# vfd-driver.net
KiCad netlist of a schematic drawn in EAGLE
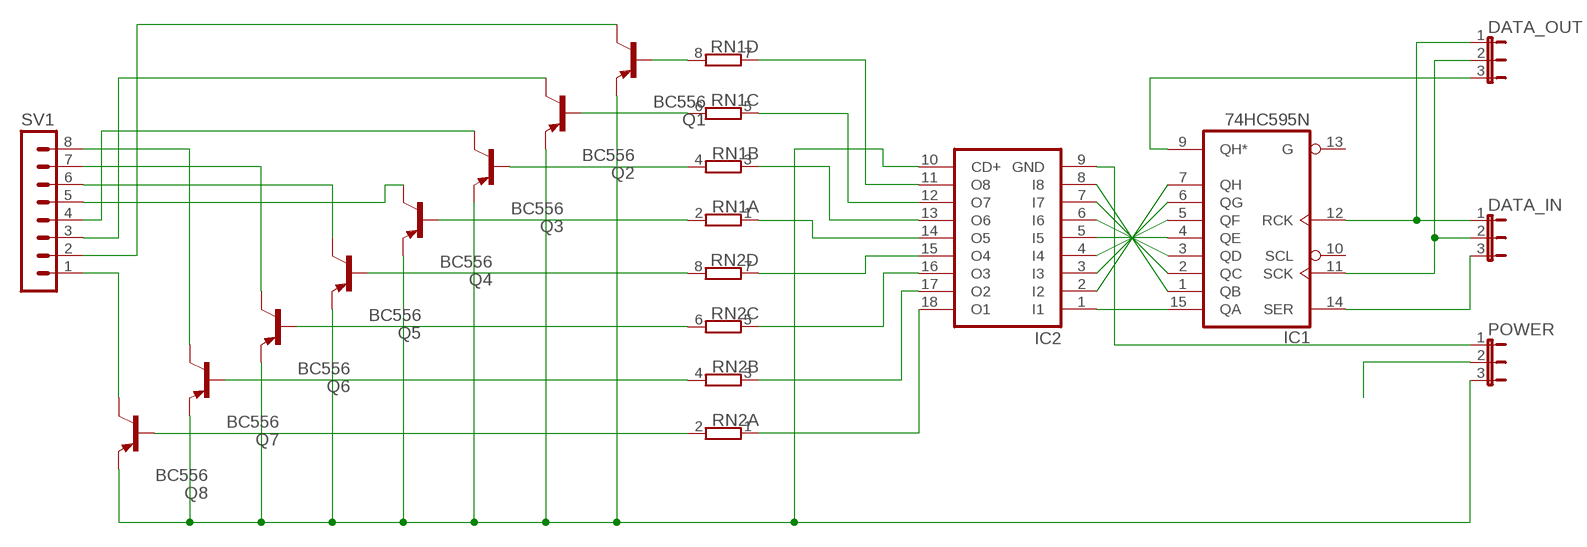
[diagram p0: schematic, sheet 1]

(export (version "E")
  (design (tool "Eeschema 10.0.6"))
  (components
    (comp (ref "DATA_IN")
      (value "JP2E")
      (footprint "eagle-import:JP2")
      (libsource (lib "eagle-import") (part "JP2E"))
    )
    (comp (ref "DATA_OUT")
      (value "JP2E")
      (footprint "eagle-import:JP2")
      (libsource (lib "eagle-import") (part "JP2E"))
    )
    (comp (ref "IC1")
      (value "74HC595N")
      (footprint "eagle-import:DIL16")
      (libsource (lib "eagle-import") (part "74595NHC"))
    )
    (comp (ref "IC2")
      (value "ULN2803A")
      (footprint "eagle-import:DIL18")
      (libsource (lib "eagle-import") (part "ULN2803A"))
    )
    (comp (ref "POWER")
      (value "JP2E")
      (footprint "eagle-import:JP2")
      (libsource (lib "eagle-import") (part "JP2E"))
    )
    (comp (ref "Q1")
      (value "BC556")
      (footprint "eagle-import:TO92-EBC")
      (libsource (lib "eagle-import") (part "BC556"))
    )
    (comp (ref "Q2")
      (value "BC556")
      (footprint "eagle-import:TO92-EBC")
      (libsource (lib "eagle-import") (part "BC556"))
    )
    (comp (ref "Q3")
      (value "BC556")
      (footprint "eagle-import:TO92-EBC")
      (libsource (lib "eagle-import") (part "BC556"))
    )
    (comp (ref "Q4")
      (value "BC556")
      (footprint "eagle-import:TO92-EBC")
      (libsource (lib "eagle-import") (part "BC556"))
    )
    (comp (ref "Q5")
      (value "BC556")
      (footprint "eagle-import:TO92-EBC")
      (libsource (lib "eagle-import") (part "BC556"))
    )
    (comp (ref "Q6")
      (value "BC556")
      (footprint "eagle-import:TO92-EBC")
      (libsource (lib "eagle-import") (part "BC556"))
    )
    (comp (ref "Q7")
      (value "BC556")
      (footprint "eagle-import:TO92-EBC")
      (libsource (lib "eagle-import") (part "BC556"))
    )
    (comp (ref "Q8")
      (value "BC556")
      (footprint "eagle-import:TO92-EBC")
      (libsource (lib "eagle-import") (part "BC556"))
    )
    (comp (ref "RN1")
      (value "E4R")
      (footprint "eagle-import:SIL8")
      (libsource (lib "eagle-import") (part "E4R"))
    )
    (comp (ref "RN2")
      (value "E4R")
      (footprint "eagle-import:SIL8")
      (libsource (lib "eagle-import") (part "E4R"))
    )
    (comp (ref "SV1")
      (value "MA08-1")
      (footprint "eagle-import:MA08-1")
      (libsource (lib "eagle-import") (part "MA08-1"))
    )
  )
  (nets
    (net (code "1") (name "Net-(IC1A-QA)") (class "Default")
      (node (ref "IC1") (pin "15") (pinfunction "QA_15") (pintype "tri_state"))
      (node (ref "IC2") (pin "1") (pinfunction "I1_1") (pintype "input"))
    )
    (net (code "2") (name "Net-(IC1A-QB)") (class "Default")
      (node (ref "IC1") (pin "1") (pinfunction "QB_1") (pintype "tri_state"))
      (node (ref "IC2") (pin "8") (pinfunction "I8_8") (pintype "input"))
    )
    (net (code "3") (name "Net-(IC1A-QC)") (class "Default")
      (node (ref "IC1") (pin "2") (pinfunction "QC_2") (pintype "tri_state"))
      (node (ref "IC2") (pin "7") (pinfunction "I7_7") (pintype "input"))
    )
    (net (code "4") (name "Net-(IC1A-QD)") (class "Default")
      (node (ref "IC1") (pin "3") (pinfunction "QD_3") (pintype "tri_state"))
      (node (ref "IC2") (pin "6") (pinfunction "I6_6") (pintype "input"))
    )
    (net (code "5") (name "Net-(IC1A-QE)") (class "Default")
      (node (ref "IC1") (pin "4") (pinfunction "QE_4") (pintype "tri_state"))
      (node (ref "IC2") (pin "5") (pinfunction "I5_5") (pintype "input"))
    )
    (net (code "6") (name "Net-(IC1A-QF)") (class "Default")
      (node (ref "IC1") (pin "5") (pinfunction "QF_5") (pintype "tri_state"))
      (node (ref "IC2") (pin "4") (pinfunction "I4_4") (pintype "input"))
    )
    (net (code "7") (name "Net-(IC1A-QG)") (class "Default")
      (node (ref "IC1") (pin "6") (pinfunction "QG_6") (pintype "tri_state"))
      (node (ref "IC2") (pin "3") (pinfunction "I3_3") (pintype "input"))
    )
    (net (code "8") (name "Net-(IC1A-QH)") (class "Default")
      (node (ref "IC1") (pin "7") (pinfunction "QH_7") (pintype "tri_state"))
      (node (ref "IC2") (pin "2") (pinfunction "I2_2") (pintype "input"))
    )
    (net (code "9") (name "Net-(IC1A-QH*)") (class "Default")
      (node (ref "DATA_OUT") (pin "3") (pinfunction "3_3") (pintype "passive"))
      (node (ref "IC1") (pin "9") (pinfunction "QH*_9") (pintype "tri_state"))
    )
    (net (code "10") (name "Net-(IC1A-RCK)") (class "Default")
      (node (ref "DATA_IN") (pin "1") (pinfunction "1_1") (pintype "passive"))
      (node (ref "DATA_OUT") (pin "1") (pinfunction "1_1") (pintype "passive"))
      (node (ref "IC1") (pin "12") (pinfunction "RCK_12") (pintype "input"))
    )
    (net (code "11") (name "Net-(IC1A-SCK)") (class "Default")
      (node (ref "DATA_IN") (pin "2") (pinfunction "2_2") (pintype "passive"))
      (node (ref "DATA_OUT") (pin "2") (pinfunction "2_2") (pintype "passive"))
      (node (ref "IC1") (pin "11") (pinfunction "SCK_11") (pintype "input"))
    )
    (net (code "12") (name "Net-(IC1A-SER)") (class "Default")
      (node (ref "DATA_IN") (pin "3") (pinfunction "3_3") (pintype "passive"))
      (node (ref "IC1") (pin "14") (pinfunction "SER_14") (pintype "input"))
    )
    (net (code "13") (name "Net-(IC2-CD+)") (class "Default")
      (node (ref "IC2") (pin "10") (pinfunction "CD+_10") (pintype "passive"))
      (node (ref "POWER") (pin "3") (pinfunction "3_3") (pintype "passive"))
      (node (ref "Q1") (pin "E") (pinfunction "E_E") (pintype "passive"))
      (node (ref "Q2") (pin "E") (pinfunction "E_E") (pintype "passive"))
      (node (ref "Q3") (pin "E") (pinfunction "E_E") (pintype "passive"))
      (node (ref "Q4") (pin "E") (pinfunction "E_E") (pintype "passive"))
      (node (ref "Q5") (pin "E") (pinfunction "E_E") (pintype "passive"))
      (node (ref "Q6") (pin "E") (pinfunction "E_E") (pintype "passive"))
      (node (ref "Q7") (pin "E") (pinfunction "E_E") (pintype "passive"))
      (node (ref "Q8") (pin "E") (pinfunction "E_E") (pintype "passive"))
    )
    (net (code "14") (name "Net-(IC2-GND)") (class "Default")
      (node (ref "IC2") (pin "9") (pinfunction "GND_9") (pintype "power_in"))
      (node (ref "POWER") (pin "1") (pinfunction "1_1") (pintype "passive"))
    )
    (net (code "15") (name "Net-(IC2-O1)") (class "Default")
      (node (ref "IC2") (pin "18") (pinfunction "O1_18") (pintype "open_collector"))
      (node (ref "RN2") (pin "1") (pinfunction "1_1") (pintype "passive"))
    )
    (net (code "16") (name "Net-(IC2-O2)") (class "Default")
      (node (ref "IC2") (pin "17") (pinfunction "O2_17") (pintype "open_collector"))
      (node (ref "RN2") (pin "3") (pinfunction "1_3") (pintype "passive"))
    )
    (net (code "17") (name "Net-(IC2-O3)") (class "Default")
      (node (ref "IC2") (pin "16") (pinfunction "O3_16") (pintype "open_collector"))
      (node (ref "RN2") (pin "5") (pinfunction "1_5") (pintype "passive"))
    )
    (net (code "18") (name "Net-(IC2-O4)") (class "Default")
      (node (ref "IC2") (pin "15") (pinfunction "O4_15") (pintype "open_collector"))
      (node (ref "RN2") (pin "7") (pinfunction "1_7") (pintype "passive"))
    )
    (net (code "19") (name "Net-(IC2-O5)") (class "Default")
      (node (ref "IC2") (pin "14") (pinfunction "O5_14") (pintype "open_collector"))
      (node (ref "RN1") (pin "1") (pinfunction "1_1") (pintype "passive"))
    )
    (net (code "20") (name "Net-(IC2-O6)") (class "Default")
      (node (ref "IC2") (pin "13") (pinfunction "O6_13") (pintype "open_collector"))
      (node (ref "RN1") (pin "3") (pinfunction "1_3") (pintype "passive"))
    )
    (net (code "21") (name "Net-(IC2-O7)") (class "Default")
      (node (ref "IC2") (pin "12") (pinfunction "O7_12") (pintype "open_collector"))
      (node (ref "RN1") (pin "5") (pinfunction "1_5") (pintype "passive"))
    )
    (net (code "22") (name "Net-(IC2-O8)") (class "Default")
      (node (ref "IC2") (pin "11") (pinfunction "O8_11") (pintype "open_collector"))
      (node (ref "RN1") (pin "7") (pinfunction "1_7") (pintype "passive"))
    )
    (net (code "23") (name "Net-(Q1-PadC)") (class "Default")
      (node (ref "Q1") (pin "C") (pinfunction "C_C") (pintype "passive"))
      (node (ref "SV1") (pin "2") (pinfunction "2_2") (pintype "passive"))
    )
    (net (code "24") (name "Net-(Q2-PadC)") (class "Default")
      (node (ref "Q2") (pin "C") (pinfunction "C_C") (pintype "passive"))
      (node (ref "SV1") (pin "3") (pinfunction "3_3") (pintype "passive"))
    )
    (net (code "25") (name "Net-(Q3-PadC)") (class "Default")
      (node (ref "Q3") (pin "C") (pinfunction "C_C") (pintype "passive"))
      (node (ref "SV1") (pin "4") (pinfunction "4_4") (pintype "passive"))
    )
    (net (code "26") (name "Net-(Q4-PadB)") (class "Default")
      (node (ref "Q4") (pin "B") (pinfunction "B_B") (pintype "passive"))
      (node (ref "RN1") (pin "2") (pinfunction "2_2") (pintype "passive"))
    )
    (net (code "27") (name "Net-(Q4-PadC)") (class "Default")
      (node (ref "Q4") (pin "C") (pinfunction "C_C") (pintype "passive"))
      (node (ref "SV1") (pin "5") (pinfunction "5_5") (pintype "passive"))
    )
    (net (code "28") (name "Net-(Q5-PadC)") (class "Default")
      (node (ref "Q5") (pin "C") (pinfunction "C_C") (pintype "passive"))
      (node (ref "SV1") (pin "6") (pinfunction "6_6") (pintype "passive"))
    )
    (net (code "29") (name "Net-(Q6-PadC)") (class "Default")
      (node (ref "Q6") (pin "C") (pinfunction "C_C") (pintype "passive"))
      (node (ref "SV1") (pin "7") (pinfunction "7_7") (pintype "passive"))
    )
    (net (code "30") (name "Net-(Q7-PadC)") (class "Default")
      (node (ref "Q7") (pin "C") (pinfunction "C_C") (pintype "passive"))
      (node (ref "SV1") (pin "8") (pinfunction "8_8") (pintype "passive"))
    )
    (net (code "31") (name "Net-(Q8-PadB)") (class "Default")
      (node (ref "Q8") (pin "B") (pinfunction "B_B") (pintype "passive"))
      (node (ref "RN2") (pin "2") (pinfunction "2_2") (pintype "passive"))
    )
    (net (code "32") (name "Net-(Q8-PadC)") (class "Default")
      (node (ref "Q8") (pin "C") (pinfunction "C_C") (pintype "passive"))
      (node (ref "SV1") (pin "1") (pinfunction "1_1") (pintype "passive"))
    )
    (net (code "33") (name "Net-(RN1B-2)") (class "Default")
      (node (ref "Q3") (pin "B") (pinfunction "B_B") (pintype "passive"))
      (node (ref "RN1") (pin "4") (pinfunction "2_4") (pintype "passive"))
    )
    (net (code "34") (name "Net-(RN1C-2)") (class "Default")
      (node (ref "Q2") (pin "B") (pinfunction "B_B") (pintype "passive"))
      (node (ref "RN1") (pin "6") (pinfunction "2_6") (pintype "passive"))
    )
    (net (code "35") (name "Net-(RN1D-2)") (class "Default")
      (node (ref "Q1") (pin "B") (pinfunction "B_B") (pintype "passive"))
      (node (ref "RN1") (pin "8") (pinfunction "2_8") (pintype "passive"))
    )
    (net (code "36") (name "Net-(RN2B-2)") (class "Default")
      (node (ref "Q7") (pin "B") (pinfunction "B_B") (pintype "passive"))
      (node (ref "RN2") (pin "4") (pinfunction "2_4") (pintype "passive"))
    )
    (net (code "37") (name "Net-(RN2C-2)") (class "Default")
      (node (ref "Q6") (pin "B") (pinfunction "B_B") (pintype "passive"))
      (node (ref "RN2") (pin "6") (pinfunction "2_6") (pintype "passive"))
    )
    (net (code "38") (name "Net-(RN2D-2)") (class "Default")
      (node (ref "Q5") (pin "B") (pinfunction "B_B") (pintype "passive"))
      (node (ref "RN2") (pin "8") (pinfunction "2_8") (pintype "passive"))
    )
    (net (code "39") (name "unconnected-(IC1A-G-Pad13)") (class "Default")
      (node (ref "IC1") (pin "13") (pinfunction "G_13") (pintype "input"))
    )
    (net (code "40") (name "unconnected-(IC1A-SCL-Pad10)") (class "Default")
      (node (ref "IC1") (pin "10") (pinfunction "SCL_10") (pintype "input"))
    )
    (net (code "41") (name "unconnected-(POWER-Pad2)") (class "Default")
      (node (ref "POWER") (pin "2") (pinfunction "2_2") (pintype "passive"))
    )
  )
)
